# 2.net
KiCad netlist of a schematic drawn in Altium Designer
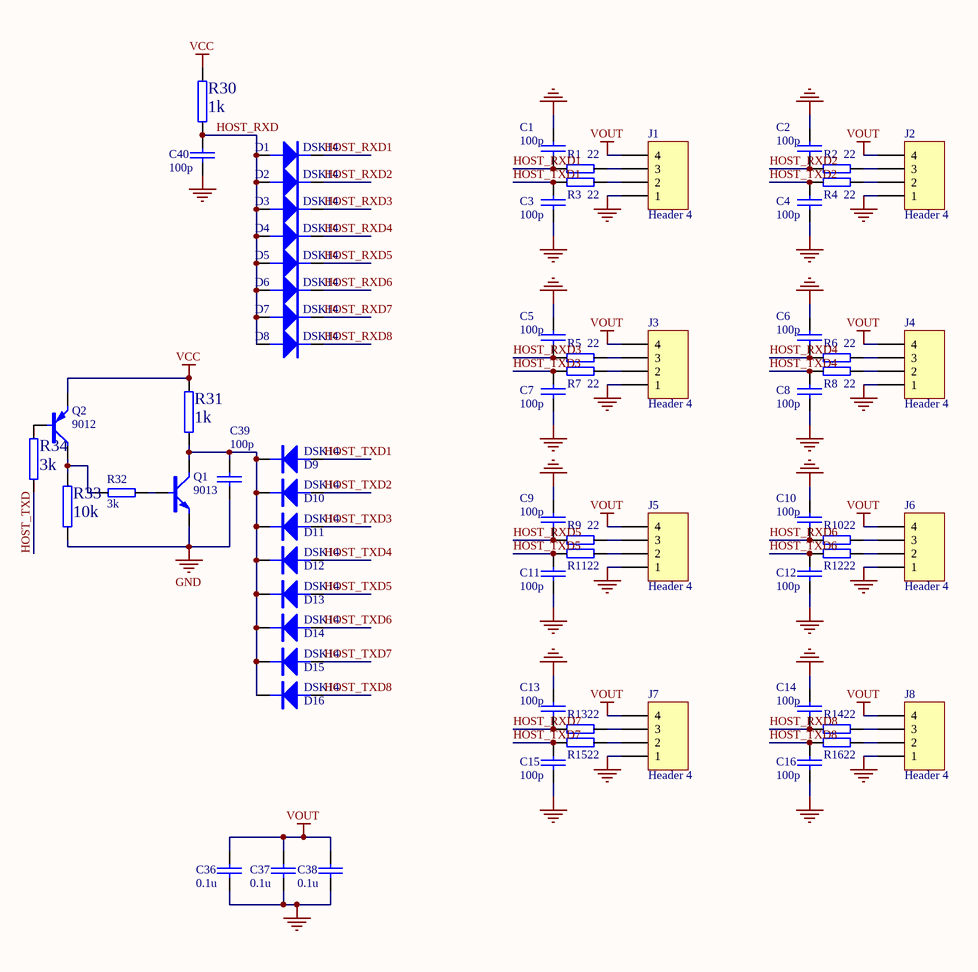
[diagram p0: 主机板2.SchDoc]

(export (version "E")
  (design (tool "Eeschema 10.0.6"))
  (components
    (comp (ref "C1")
      (value "100p")
      (footprint "C0603")
      (description "无极性电容")
      (libsource (lib "CBB_Lib_SCH") (part "CAP"))
    )
    (comp (ref "C2")
      (value "100p")
      (footprint "C0603")
      (description "无极性电容")
      (libsource (lib "CBB_Lib_SCH") (part "CAP"))
    )
    (comp (ref "C3")
      (value "100p")
      (footprint "C0603")
      (description "无极性电容")
      (libsource (lib "CBB_Lib_SCH") (part "CAP"))
    )
    (comp (ref "C4")
      (value "100p")
      (footprint "C0603")
      (description "无极性电容")
      (libsource (lib "CBB_Lib_SCH") (part "CAP"))
    )
    (comp (ref "C5")
      (value "100p")
      (footprint "C0603")
      (description "无极性电容")
      (libsource (lib "CBB_Lib_SCH") (part "CAP"))
    )
    (comp (ref "C6")
      (value "100p")
      (footprint "C0603")
      (description "无极性电容")
      (libsource (lib "CBB_Lib_SCH") (part "CAP"))
    )
    (comp (ref "C7")
      (value "100p")
      (footprint "C0603")
      (description "无极性电容")
      (libsource (lib "CBB_Lib_SCH") (part "CAP"))
    )
    (comp (ref "C8")
      (value "100p")
      (footprint "C0603")
      (description "无极性电容")
      (libsource (lib "CBB_Lib_SCH") (part "CAP"))
    )
    (comp (ref "C9")
      (value "100p")
      (footprint "C0603")
      (description "无极性电容")
      (libsource (lib "CBB_Lib_SCH") (part "CAP"))
    )
    (comp (ref "C10")
      (value "100p")
      (footprint "C0603")
      (description "无极性电容")
      (libsource (lib "CBB_Lib_SCH") (part "CAP"))
    )
    (comp (ref "C11")
      (value "100p")
      (footprint "C0603")
      (description "无极性电容")
      (libsource (lib "CBB_Lib_SCH") (part "CAP"))
    )
    (comp (ref "C12")
      (value "100p")
      (footprint "C0603")
      (description "无极性电容")
      (libsource (lib "CBB_Lib_SCH") (part "CAP"))
    )
    (comp (ref "C13")
      (value "100p")
      (footprint "C0603")
      (description "无极性电容")
      (libsource (lib "CBB_Lib_SCH") (part "CAP"))
    )
    (comp (ref "C14")
      (value "100p")
      (footprint "C0603")
      (description "无极性电容")
      (libsource (lib "CBB_Lib_SCH") (part "CAP"))
    )
    (comp (ref "C15")
      (value "100p")
      (footprint "C0603")
      (description "无极性电容")
      (libsource (lib "CBB_Lib_SCH") (part "CAP"))
    )
    (comp (ref "C16")
      (value "100p")
      (footprint "C0603")
      (description "无极性电容")
      (libsource (lib "CBB_Lib_SCH") (part "CAP"))
    )
    (comp (ref "C36")
      (value "0.1u")
      (footprint "C0603")
      (description "无极性电容")
      (libsource (lib "CBB_Lib_SCH") (part "CAP"))
    )
    (comp (ref "C37")
      (value "0.1u")
      (footprint "C0603")
      (description "无极性电容")
      (libsource (lib "CBB_Lib_SCH") (part "CAP"))
    )
    (comp (ref "C38")
      (value "0.1u")
      (footprint "C0603")
      (description "无极性电容")
      (libsource (lib "CBB_Lib_SCH") (part "CAP"))
    )
    (comp (ref "C39")
      (value "100p")
      (footprint "C0603")
      (description "无极性电容")
      (libsource (lib "CBB_Lib_SCH") (part "CAP"))
    )
    (comp (ref "C40")
      (value "100p")
      (footprint "C0603")
      (description "无极性电容")
      (libsource (lib "CBB_Lib_SCH") (part "CAP"))
    )
    (comp (ref "D1")
      (value "DSK14")
      (footprint "SOD-123FL")
      (description "二极管，Diode")
      (libsource (lib "CBB_Lib_SCH") (part "DIODE"))
    )
    (comp (ref "D2")
      (value "DSK14")
      (footprint "SOD-123FL")
      (description "二极管，Diode")
      (libsource (lib "CBB_Lib_SCH") (part "DIODE"))
    )
    (comp (ref "D3")
      (value "DSK14")
      (footprint "SOD-123FL")
      (description "二极管，Diode")
      (libsource (lib "CBB_Lib_SCH") (part "DIODE"))
    )
    (comp (ref "D4")
      (value "DSK14")
      (footprint "SOD-123FL")
      (description "二极管，Diode")
      (libsource (lib "CBB_Lib_SCH") (part "DIODE"))
    )
    (comp (ref "D5")
      (value "DSK14")
      (footprint "SOD-123FL")
      (description "二极管，Diode")
      (libsource (lib "CBB_Lib_SCH") (part "DIODE"))
    )
    (comp (ref "D6")
      (value "DSK14")
      (footprint "SOD-123FL")
      (description "二极管，Diode")
      (libsource (lib "CBB_Lib_SCH") (part "DIODE"))
    )
    (comp (ref "D7")
      (value "DSK14")
      (footprint "SOD-123FL")
      (description "二极管，Diode")
      (libsource (lib "CBB_Lib_SCH") (part "DIODE"))
    )
    (comp (ref "D8")
      (value "DSK14")
      (footprint "SOD-123FL")
      (description "二极管，Diode")
      (libsource (lib "CBB_Lib_SCH") (part "DIODE"))
    )
    (comp (ref "D9")
      (value "DSK14")
      (footprint "SOD-123FL")
      (description "二极管，Diode")
      (libsource (lib "CBB_Lib_SCH") (part "DIODE"))
    )
    (comp (ref "D10")
      (value "DSK14")
      (footprint "SOD-123FL")
      (description "二极管，Diode")
      (libsource (lib "CBB_Lib_SCH") (part "DIODE"))
    )
    (comp (ref "D11")
      (value "DSK14")
      (footprint "SOD-123FL")
      (description "二极管，Diode")
      (libsource (lib "CBB_Lib_SCH") (part "DIODE"))
    )
    (comp (ref "D12")
      (value "DSK14")
      (footprint "SOD-123FL")
      (description "二极管，Diode")
      (libsource (lib "CBB_Lib_SCH") (part "DIODE"))
    )
    (comp (ref "D13")
      (value "DSK14")
      (footprint "SOD-123FL")
      (description "二极管，Diode")
      (libsource (lib "CBB_Lib_SCH") (part "DIODE"))
    )
    (comp (ref "D14")
      (value "DSK14")
      (footprint "SOD-123FL")
      (description "二极管，Diode")
      (libsource (lib "CBB_Lib_SCH") (part "DIODE"))
    )
    (comp (ref "D15")
      (value "DSK14")
      (footprint "SOD-123FL")
      (description "二极管，Diode")
      (libsource (lib "CBB_Lib_SCH") (part "DIODE"))
    )
    (comp (ref "D16")
      (value "DSK14")
      (footprint "SOD-123FL")
      (description "二极管，Diode")
      (libsource (lib "CBB_Lib_SCH") (part "DIODE"))
    )
    (comp (ref "J1")
      (value "Header 4")
      (footprint "HDX4-2.54")
      (description "Header, 4-Pin")
      (fields (field (name "PUBLISHER") "Altium Limited"))
      (libsource (lib "Miscellaneous Connectors") (part "Header 4"))
    )
    (comp (ref "J2")
      (value "Header 4")
      (footprint "HDX4-2.54")
      (description "Header, 4-Pin")
      (fields (field (name "PUBLISHER") "Altium Limited"))
      (libsource (lib "Miscellaneous Connectors") (part "Header 4"))
    )
    (comp (ref "J3")
      (value "Header 4")
      (footprint "HDX4-2.54")
      (description "Header, 4-Pin")
      (fields (field (name "PUBLISHER") "Altium Limited"))
      (libsource (lib "Miscellaneous Connectors") (part "Header 4"))
    )
    (comp (ref "J4")
      (value "Header 4")
      (footprint "HDX4-2.54")
      (description "Header, 4-Pin")
      (fields (field (name "PUBLISHER") "Altium Limited"))
      (libsource (lib "Miscellaneous Connectors") (part "Header 4"))
    )
    (comp (ref "J5")
      (value "Header 4")
      (footprint "HDX4-2.54")
      (description "Header, 4-Pin")
      (fields (field (name "PUBLISHER") "Altium Limited"))
      (libsource (lib "Miscellaneous Connectors") (part "Header 4"))
    )
    (comp (ref "J6")
      (value "Header 4")
      (footprint "HDX4-2.54")
      (description "Header, 4-Pin")
      (fields (field (name "PUBLISHER") "Altium Limited"))
      (libsource (lib "Miscellaneous Connectors") (part "Header 4"))
    )
    (comp (ref "J7")
      (value "Header 4")
      (footprint "HDX4-2.54")
      (description "Header, 4-Pin")
      (fields (field (name "PUBLISHER") "Altium Limited"))
      (libsource (lib "Miscellaneous Connectors") (part "Header 4"))
    )
    (comp (ref "J8")
      (value "Header 4")
      (footprint "HDX4-2.54")
      (description "Header, 4-Pin")
      (fields (field (name "PUBLISHER") "Altium Limited"))
      (libsource (lib "Miscellaneous Connectors") (part "Header 4"))
    )
    (comp (ref "Q1")
      (value "9013")
      (footprint "CBB_Lib_PCB:SOT-23-TRAN")
      (description "NPN Transistor")
      (libsource (lib "CBB_Lib_SCH") (part "NPN-S"))
    )
    (comp (ref "Q2") (value "9012") (footprint "SOT23-9013") (libsource (lib "chip") (part "9012")))
    (comp (ref "R1") (value "22") (footprint "R0603") (libsource (lib "CBB_Lib_SCH") (part "RES")))
    (comp (ref "R2") (value "22") (footprint "R0603") (libsource (lib "CBB_Lib_SCH") (part "RES")))
    (comp (ref "R3") (value "22") (footprint "R0603") (libsource (lib "CBB_Lib_SCH") (part "RES")))
    (comp (ref "R4") (value "22") (footprint "R0603") (libsource (lib "CBB_Lib_SCH") (part "RES")))
    (comp (ref "R5") (value "22") (footprint "R0603") (libsource (lib "CBB_Lib_SCH") (part "RES")))
    (comp (ref "R6") (value "22") (footprint "R0603") (libsource (lib "CBB_Lib_SCH") (part "RES")))
    (comp (ref "R7") (value "22") (footprint "R0603") (libsource (lib "CBB_Lib_SCH") (part "RES")))
    (comp (ref "R8") (value "22") (footprint "R0603") (libsource (lib "CBB_Lib_SCH") (part "RES")))
    (comp (ref "R9") (value "22") (footprint "R0603") (libsource (lib "CBB_Lib_SCH") (part "RES")))
    (comp (ref "R10") (value "22") (footprint "R0603") (libsource (lib "CBB_Lib_SCH") (part "RES")))
    (comp (ref "R11") (value "22") (footprint "R0603") (libsource (lib "CBB_Lib_SCH") (part "RES")))
    (comp (ref "R12") (value "22") (footprint "R0603") (libsource (lib "CBB_Lib_SCH") (part "RES")))
    (comp (ref "R13") (value "22") (footprint "R0603") (libsource (lib "CBB_Lib_SCH") (part "RES")))
    (comp (ref "R14") (value "22") (footprint "R0603") (libsource (lib "CBB_Lib_SCH") (part "RES")))
    (comp (ref "R15") (value "22") (footprint "R0603") (libsource (lib "CBB_Lib_SCH") (part "RES")))
    (comp (ref "R16") (value "22") (footprint "R0603") (libsource (lib "CBB_Lib_SCH") (part "RES")))
    (comp (ref "R30") (value "1k") (footprint "r0603") (libsource (lib "PCB_Project1_1") (part "RES2")))
    (comp (ref "R31") (value "1k") (footprint "r0603") (libsource (lib "PCB_Project1_1") (part "RES2")))
    (comp (ref "R32") (value "3k") (footprint "R0603") (libsource (lib "CBB_Lib_SCH") (part "RES")))
    (comp (ref "R33") (value "10k") (footprint "r0603") (libsource (lib "PCB_Project1_1") (part "RES2")))
    (comp (ref "R34") (value "3k") (footprint "r0603") (libsource (lib "PCB_Project1_1") (part "RES2")))
  )
  (nets
    (net (code "1") (name "/HOST_RXD") (class "Default")
      (node (ref "C40") (pin "2") (pintype "passive"))
      (node (ref "D1") (pin "1") (pinfunction "A_1") (pintype "passive"))
      (node (ref "D2") (pin "1") (pinfunction "A_1") (pintype "passive"))
      (node (ref "D3") (pin "1") (pinfunction "A_1") (pintype "passive"))
      (node (ref "D4") (pin "1") (pinfunction "A_1") (pintype "passive"))
      (node (ref "D5") (pin "1") (pinfunction "A_1") (pintype "passive"))
      (node (ref "D6") (pin "1") (pinfunction "A_1") (pintype "passive"))
      (node (ref "D7") (pin "1") (pinfunction "A_1") (pintype "passive"))
      (node (ref "D8") (pin "1") (pinfunction "A_1") (pintype "passive"))
      (node (ref "R30") (pin "2") (pinfunction "2_2") (pintype "passive"))
    )
    (net (code "2") (name "/HOST_RXD1") (class "Default")
      (node (ref "C1") (pin "2") (pintype "passive"))
      (node (ref "D1") (pin "2") (pinfunction "K_2") (pintype "passive"))
      (node (ref "R1") (pin "1") (pintype "passive"))
    )
    (net (code "3") (name "/HOST_RXD2") (class "Default")
      (node (ref "C2") (pin "2") (pintype "passive"))
      (node (ref "D2") (pin "2") (pinfunction "K_2") (pintype "passive"))
      (node (ref "R2") (pin "1") (pintype "passive"))
    )
    (net (code "4") (name "/HOST_RXD3") (class "Default")
      (node (ref "C5") (pin "2") (pintype "passive"))
      (node (ref "D3") (pin "2") (pinfunction "K_2") (pintype "passive"))
      (node (ref "R5") (pin "1") (pintype "passive"))
    )
    (net (code "5") (name "/HOST_RXD4") (class "Default")
      (node (ref "C6") (pin "2") (pintype "passive"))
      (node (ref "D4") (pin "2") (pinfunction "K_2") (pintype "passive"))
      (node (ref "R6") (pin "1") (pintype "passive"))
    )
    (net (code "6") (name "/HOST_RXD5") (class "Default")
      (node (ref "C9") (pin "2") (pintype "passive"))
      (node (ref "D5") (pin "2") (pinfunction "K_2") (pintype "passive"))
      (node (ref "R9") (pin "1") (pintype "passive"))
    )
    (net (code "7") (name "/HOST_RXD6") (class "Default")
      (node (ref "C10") (pin "2") (pintype "passive"))
      (node (ref "D6") (pin "2") (pinfunction "K_2") (pintype "passive"))
      (node (ref "R10") (pin "1") (pintype "passive"))
    )
    (net (code "8") (name "/HOST_RXD7") (class "Default")
      (node (ref "C13") (pin "2") (pintype "passive"))
      (node (ref "D7") (pin "2") (pinfunction "K_2") (pintype "passive"))
      (node (ref "R13") (pin "1") (pintype "passive"))
    )
    (net (code "9") (name "/HOST_RXD8") (class "Default")
      (node (ref "C14") (pin "2") (pintype "passive"))
      (node (ref "D8") (pin "2") (pinfunction "K_2") (pintype "passive"))
      (node (ref "R14") (pin "1") (pintype "passive"))
    )
    (net (code "10") (name "/HOST_TXD") (class "Default")
      (node (ref "R34") (pin "1") (pinfunction "1_1") (pintype "passive"))
    )
    (net (code "11") (name "/HOST_TXD1") (class "Default")
      (node (ref "C3") (pin "2") (pintype "passive"))
      (node (ref "D9") (pin "1") (pinfunction "A_1") (pintype "passive"))
      (node (ref "R3") (pin "2") (pintype "passive"))
    )
    (net (code "12") (name "/HOST_TXD2") (class "Default")
      (node (ref "C4") (pin "2") (pintype "passive"))
      (node (ref "D10") (pin "1") (pinfunction "A_1") (pintype "passive"))
      (node (ref "R4") (pin "2") (pintype "passive"))
    )
    (net (code "13") (name "/HOST_TXD3") (class "Default")
      (node (ref "C7") (pin "2") (pintype "passive"))
      (node (ref "D11") (pin "1") (pinfunction "A_1") (pintype "passive"))
      (node (ref "R7") (pin "2") (pintype "passive"))
    )
    (net (code "14") (name "/HOST_TXD4") (class "Default")
      (node (ref "C8") (pin "2") (pintype "passive"))
      (node (ref "D12") (pin "1") (pinfunction "A_1") (pintype "passive"))
      (node (ref "R8") (pin "2") (pintype "passive"))
    )
    (net (code "15") (name "/HOST_TXD5") (class "Default")
      (node (ref "C11") (pin "2") (pintype "passive"))
      (node (ref "D13") (pin "1") (pinfunction "A_1") (pintype "passive"))
      (node (ref "R11") (pin "2") (pintype "passive"))
    )
    (net (code "16") (name "/HOST_TXD6") (class "Default")
      (node (ref "C12") (pin "2") (pintype "passive"))
      (node (ref "D14") (pin "1") (pinfunction "A_1") (pintype "passive"))
      (node (ref "R12") (pin "2") (pintype "passive"))
    )
    (net (code "17") (name "/HOST_TXD7") (class "Default")
      (node (ref "C15") (pin "2") (pintype "passive"))
      (node (ref "D15") (pin "1") (pinfunction "A_1") (pintype "passive"))
      (node (ref "R15") (pin "2") (pintype "passive"))
    )
    (net (code "18") (name "/HOST_TXD8") (class "Default")
      (node (ref "C16") (pin "2") (pintype "passive"))
      (node (ref "D16") (pin "1") (pinfunction "A_1") (pintype "passive"))
      (node (ref "R16") (pin "2") (pintype "passive"))
    )
    (net (code "19") (name "GND") (class "Default")
      (node (ref "C1") (pin "1") (pintype "passive"))
      (node (ref "C10") (pin "1") (pintype "passive"))
      (node (ref "C11") (pin "1") (pintype "passive"))
      (node (ref "C12") (pin "1") (pintype "passive"))
      (node (ref "C13") (pin "1") (pintype "passive"))
      (node (ref "C14") (pin "1") (pintype "passive"))
      (node (ref "C15") (pin "1") (pintype "passive"))
      (node (ref "C16") (pin "1") (pintype "passive"))
      (node (ref "C2") (pin "1") (pintype "passive"))
      (node (ref "C3") (pin "1") (pintype "passive"))
      (node (ref "C36") (pin "1") (pintype "passive"))
      (node (ref "C37") (pin "1") (pintype "passive"))
      (node (ref "C38") (pin "1") (pintype "passive"))
      (node (ref "C39") (pin "1") (pintype "passive"))
      (node (ref "C4") (pin "1") (pintype "passive"))
      (node (ref "C40") (pin "1") (pintype "passive"))
      (node (ref "C5") (pin "1") (pintype "passive"))
      (node (ref "C6") (pin "1") (pintype "passive"))
      (node (ref "C7") (pin "1") (pintype "passive"))
      (node (ref "C8") (pin "1") (pintype "passive"))
      (node (ref "C9") (pin "1") (pintype "passive"))
      (node (ref "J1") (pin "1") (pinfunction "1_1") (pintype "passive"))
      (node (ref "J2") (pin "1") (pinfunction "1_1") (pintype "passive"))
      (node (ref "J3") (pin "1") (pinfunction "1_1") (pintype "passive"))
      (node (ref "J4") (pin "1") (pinfunction "1_1") (pintype "passive"))
      (node (ref "J5") (pin "1") (pinfunction "1_1") (pintype "passive"))
      (node (ref "J6") (pin "1") (pinfunction "1_1") (pintype "passive"))
      (node (ref "J7") (pin "1") (pinfunction "1_1") (pintype "passive"))
      (node (ref "J8") (pin "1") (pinfunction "1_1") (pintype "passive"))
      (node (ref "Q1") (pin "E") (pinfunction "E_E") (pintype "passive"))
      (node (ref "R33") (pin "1") (pinfunction "1_1") (pintype "passive"))
    )
    (net (code "20") (name "Net-(D10-K)") (class "Default")
      (node (ref "C39") (pin "2") (pintype "passive"))
      (node (ref "D10") (pin "2") (pinfunction "K_2") (pintype "passive"))
      (node (ref "D11") (pin "2") (pinfunction "K_2") (pintype "passive"))
      (node (ref "D12") (pin "2") (pinfunction "K_2") (pintype "passive"))
      (node (ref "D13") (pin "2") (pinfunction "K_2") (pintype "passive"))
      (node (ref "D14") (pin "2") (pinfunction "K_2") (pintype "passive"))
      (node (ref "D15") (pin "2") (pinfunction "K_2") (pintype "passive"))
      (node (ref "D16") (pin "2") (pinfunction "K_2") (pintype "passive"))
      (node (ref "D9") (pin "2") (pinfunction "K_2") (pintype "passive"))
      (node (ref "Q1") (pin "C") (pinfunction "C_C") (pintype "passive"))
      (node (ref "R31") (pin "2") (pinfunction "2_2") (pintype "passive"))
    )
    (net (code "21") (name "Net-(J1-Pad2)") (class "Default")
      (node (ref "J1") (pin "2") (pinfunction "2_2") (pintype "passive"))
      (node (ref "R3") (pin "1") (pintype "passive"))
    )
    (net (code "22") (name "Net-(J1-Pad3)") (class "Default")
      (node (ref "J1") (pin "3") (pinfunction "3_3") (pintype "passive"))
      (node (ref "R1") (pin "2") (pintype "passive"))
    )
    (net (code "23") (name "Net-(J2-Pad2)") (class "Default")
      (node (ref "J2") (pin "2") (pinfunction "2_2") (pintype "passive"))
      (node (ref "R4") (pin "1") (pintype "passive"))
    )
    (net (code "24") (name "Net-(J2-Pad3)") (class "Default")
      (node (ref "J2") (pin "3") (pinfunction "3_3") (pintype "passive"))
      (node (ref "R2") (pin "2") (pintype "passive"))
    )
    (net (code "25") (name "Net-(J3-Pad2)") (class "Default")
      (node (ref "J3") (pin "2") (pinfunction "2_2") (pintype "passive"))
      (node (ref "R7") (pin "1") (pintype "passive"))
    )
    (net (code "26") (name "Net-(J3-Pad3)") (class "Default")
      (node (ref "J3") (pin "3") (pinfunction "3_3") (pintype "passive"))
      (node (ref "R5") (pin "2") (pintype "passive"))
    )
    (net (code "27") (name "Net-(J4-Pad2)") (class "Default")
      (node (ref "J4") (pin "2") (pinfunction "2_2") (pintype "passive"))
      (node (ref "R8") (pin "1") (pintype "passive"))
    )
    (net (code "28") (name "Net-(J4-Pad3)") (class "Default")
      (node (ref "J4") (pin "3") (pinfunction "3_3") (pintype "passive"))
      (node (ref "R6") (pin "2") (pintype "passive"))
    )
    (net (code "29") (name "Net-(J5-Pad2)") (class "Default")
      (node (ref "J5") (pin "2") (pinfunction "2_2") (pintype "passive"))
      (node (ref "R11") (pin "1") (pintype "passive"))
    )
    (net (code "30") (name "Net-(J5-Pad3)") (class "Default")
      (node (ref "J5") (pin "3") (pinfunction "3_3") (pintype "passive"))
      (node (ref "R9") (pin "2") (pintype "passive"))
    )
    (net (code "31") (name "Net-(J6-Pad2)") (class "Default")
      (node (ref "J6") (pin "2") (pinfunction "2_2") (pintype "passive"))
      (node (ref "R12") (pin "1") (pintype "passive"))
    )
    (net (code "32") (name "Net-(J6-Pad3)") (class "Default")
      (node (ref "J6") (pin "3") (pinfunction "3_3") (pintype "passive"))
      (node (ref "R10") (pin "2") (pintype "passive"))
    )
    (net (code "33") (name "Net-(J7-Pad2)") (class "Default")
      (node (ref "J7") (pin "2") (pinfunction "2_2") (pintype "passive"))
      (node (ref "R15") (pin "1") (pintype "passive"))
    )
    (net (code "34") (name "Net-(J7-Pad3)") (class "Default")
      (node (ref "J7") (pin "3") (pinfunction "3_3") (pintype "passive"))
      (node (ref "R13") (pin "2") (pintype "passive"))
    )
    (net (code "35") (name "Net-(J8-Pad2)") (class "Default")
      (node (ref "J8") (pin "2") (pinfunction "2_2") (pintype "passive"))
      (node (ref "R16") (pin "1") (pintype "passive"))
    )
    (net (code "36") (name "Net-(J8-Pad3)") (class "Default")
      (node (ref "J8") (pin "3") (pinfunction "3_3") (pintype "passive"))
      (node (ref "R14") (pin "2") (pintype "passive"))
    )
    (net (code "37") (name "Net-(Q1-PadB)") (class "Default")
      (node (ref "Q1") (pin "B") (pinfunction "B_B") (pintype "passive"))
      (node (ref "R32") (pin "1") (pintype "passive"))
    )
    (net (code "38") (name "Net-(Q2-B)") (class "Default")
      (node (ref "Q2") (pin "2") (pinfunction "B_2") (pintype "passive"))
      (node (ref "R34") (pin "2") (pinfunction "2_2") (pintype "passive"))
    )
    (net (code "39") (name "Net-(Q2-C)") (class "Default")
      (node (ref "Q2") (pin "3") (pinfunction "C_3") (pintype "passive"))
      (node (ref "R32") (pin "2") (pintype "passive"))
      (node (ref "R33") (pin "2") (pinfunction "2_2") (pintype "passive"))
    )
    (net (code "40") (name "VCC") (class "Default")
      (node (ref "Q2") (pin "1") (pinfunction "E_1") (pintype "passive"))
      (node (ref "R30") (pin "1") (pinfunction "1_1") (pintype "passive"))
      (node (ref "R31") (pin "1") (pinfunction "1_1") (pintype "passive"))
    )
    (net (code "41") (name "VOUT") (class "Default")
      (node (ref "C36") (pin "2") (pintype "passive"))
      (node (ref "C37") (pin "2") (pintype "passive"))
      (node (ref "C38") (pin "2") (pintype "passive"))
      (node (ref "J1") (pin "4") (pinfunction "4_4") (pintype "passive"))
      (node (ref "J2") (pin "4") (pinfunction "4_4") (pintype "passive"))
      (node (ref "J3") (pin "4") (pinfunction "4_4") (pintype "passive"))
      (node (ref "J4") (pin "4") (pinfunction "4_4") (pintype "passive"))
      (node (ref "J5") (pin "4") (pinfunction "4_4") (pintype "passive"))
      (node (ref "J6") (pin "4") (pinfunction "4_4") (pintype "passive"))
      (node (ref "J7") (pin "4") (pinfunction "4_4") (pintype "passive"))
      (node (ref "J8") (pin "4") (pinfunction "4_4") (pintype "passive"))
    )
  )
)
